# Clock_Multiplexer.net
KiCad netlist of a schematic drawn in EAGLE
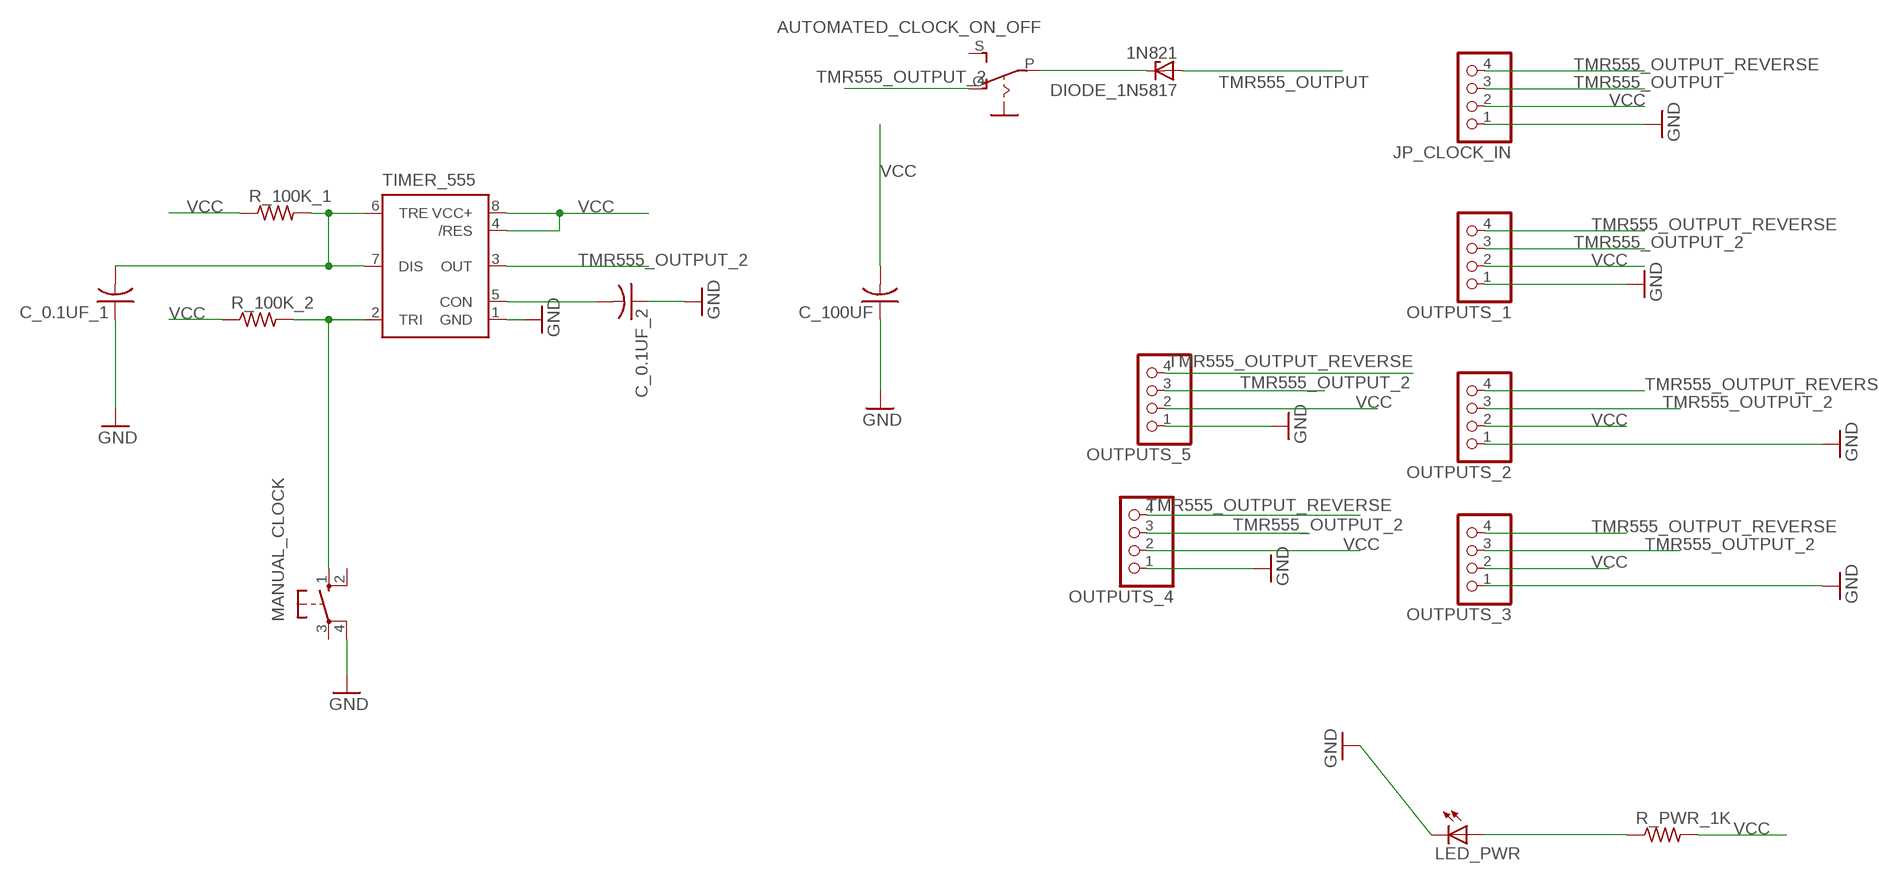
[diagram p0: schematic, sheet 1]

(export (version "E")
  (design (tool "Eeschema 10.0.6"))
  (components
    (comp (ref "AUTOMATED_CLOCK_ON_OFF")
      (value "EG1218S")
      (footprint "eagle-import:EG1218")
      (libsource (lib "eagle-import") (part "EG1218S"))
    )
    (comp (ref "C_0.1UF_1")
      (value "C-USC1206")
      (footprint "eagle-import:C1206")
      (libsource (lib "eagle-import") (part "C-USC1206"))
    )
    (comp (ref "C_0.1UF_2")
      (value "C-USC1206")
      (footprint "eagle-import:C1206")
      (libsource (lib "eagle-import") (part "C-USC1206"))
    )
    (comp (ref "C_100UF")
      (value "C-US025-030X050")
      (footprint "eagle-import:C025-030X050")
      (libsource (lib "eagle-import") (part "C-US025-030X050"))
    )
    (comp (ref "DIODE_1N5817")
      (value "1N821")
      (footprint "eagle-import:DO35Z10")
      (libsource (lib "eagle-import") (part "1N821"))
    )
    (comp (ref "JP_CLOCK_IN")
      (value "PINHD-1X4")
      (footprint "eagle-import:1X04")
      (libsource (lib "eagle-import") (part "PINHD-1X4"))
    )
    (comp (ref "LED_PWR")
      (value "LEDSMT1206")
      (footprint "eagle-import:1206")
      (libsource (lib "eagle-import") (part "LEDSMT1206"))
    )
    (comp (ref "MANUAL_CLOCK")
      (value "10-XX")
      (footprint "eagle-import:B3F-10XX")
      (fields (field (name "MPN") "B3F-1000"))
      (libsource (lib "eagle-import") (part "10-XX"))
    )
    (comp (ref "OUTPUTS_1")
      (value "PINHD-1X4")
      (footprint "eagle-import:1X04")
      (libsource (lib "eagle-import") (part "PINHD-1X4"))
    )
    (comp (ref "OUTPUTS_2")
      (value "PINHD-1X4")
      (footprint "eagle-import:1X04")
      (libsource (lib "eagle-import") (part "PINHD-1X4"))
    )
    (comp (ref "OUTPUTS_3")
      (value "PINHD-1X4")
      (footprint "eagle-import:1X04")
      (libsource (lib "eagle-import") (part "PINHD-1X4"))
    )
    (comp (ref "OUTPUTS_4")
      (value "PINHD-1X4")
      (footprint "eagle-import:1X04")
      (libsource (lib "eagle-import") (part "PINHD-1X4"))
    )
    (comp (ref "OUTPUTS_5")
      (value "PINHD-1X4")
      (footprint "eagle-import:1X04")
      (libsource (lib "eagle-import") (part "PINHD-1X4"))
    )
    (comp (ref "R_100K_1")
      (value "R-US_R1206")
      (footprint "eagle-import:R1206")
      (libsource (lib "eagle-import") (part "R-US_R1206"))
    )
    (comp (ref "R_100K_2")
      (value "R-US_R1206")
      (footprint "eagle-import:R1206")
      (libsource (lib "eagle-import") (part "R-US_R1206"))
    )
    (comp (ref "R_PWR_1K")
      (value "R-US_R1206")
      (footprint "eagle-import:R1206")
      (libsource (lib "eagle-import") (part "R-US_R1206"))
    )
    (comp (ref "TIMER_555")
      (value "NE555D")
      (footprint "eagle-import:SO08")
      (libsource (lib "eagle-import") (part "NE555D"))
    )
  )
  (nets
    (net (code "1") (name "/TMR555_OUTPUT") (class "Default")
      (node (ref "DIODE_1N5817") (pin "A") (pinfunction "A_A") (pintype "passive"))
      (node (ref "JP_CLOCK_IN") (pin "3") (pinfunction "3_3") (pintype "passive"))
    )
    (net (code "2") (name "/TMR555_OUTPUT_2") (class "Default")
      (node (ref "AUTOMATED_CLOCK_ON_OFF") (pin "O") (pinfunction "O_O") (pintype "passive"))
      (node (ref "OUTPUTS_1") (pin "3") (pinfunction "3_3") (pintype "passive"))
      (node (ref "OUTPUTS_2") (pin "3") (pinfunction "3_3") (pintype "passive"))
      (node (ref "OUTPUTS_3") (pin "3") (pinfunction "3_3") (pintype "passive"))
      (node (ref "OUTPUTS_4") (pin "3") (pinfunction "3_3") (pintype "passive"))
      (node (ref "OUTPUTS_5") (pin "3") (pinfunction "3_3") (pintype "passive"))
      (node (ref "TIMER_555") (pin "3") (pinfunction "OUT_3") (pintype "output"))
    )
    (net (code "3") (name "/TMR555_OUTPUT_REVERSE") (class "Default")
      (node (ref "JP_CLOCK_IN") (pin "4") (pinfunction "4_4") (pintype "passive"))
      (node (ref "OUTPUTS_1") (pin "4") (pinfunction "4_4") (pintype "passive"))
      (node (ref "OUTPUTS_2") (pin "4") (pinfunction "4_4") (pintype "passive"))
      (node (ref "OUTPUTS_3") (pin "4") (pinfunction "4_4") (pintype "passive"))
      (node (ref "OUTPUTS_4") (pin "4") (pinfunction "4_4") (pintype "passive"))
      (node (ref "OUTPUTS_5") (pin "4") (pinfunction "4_4") (pintype "passive"))
    )
    (net (code "4") (name "/VCC") (class "Default")
      (node (ref "C_100UF") (pin "2") (pinfunction "2_2") (pintype "passive"))
      (node (ref "JP_CLOCK_IN") (pin "2") (pinfunction "2_2") (pintype "passive"))
      (node (ref "OUTPUTS_1") (pin "2") (pinfunction "2_2") (pintype "passive"))
      (node (ref "OUTPUTS_2") (pin "2") (pinfunction "2_2") (pintype "passive"))
      (node (ref "OUTPUTS_3") (pin "2") (pinfunction "2_2") (pintype "passive"))
      (node (ref "OUTPUTS_4") (pin "2") (pinfunction "2_2") (pintype "passive"))
      (node (ref "OUTPUTS_5") (pin "2") (pinfunction "2_2") (pintype "passive"))
      (node (ref "R_100K_1") (pin "1") (pinfunction "1_1") (pintype "passive"))
      (node (ref "R_100K_2") (pin "1") (pinfunction "1_1") (pintype "passive"))
      (node (ref "R_PWR_1K") (pin "2") (pinfunction "2_2") (pintype "passive"))
      (node (ref "TIMER_555") (pin "4") (pinfunction "/RES_4") (pintype "input"))
      (node (ref "TIMER_555") (pin "8") (pinfunction "VCC+_8") (pintype "power_in"))
    )
    (net (code "5") (name "GND") (class "Default")
      (node (ref "C_0.1UF_1") (pin "1") (pinfunction "1_1") (pintype "passive"))
      (node (ref "C_0.1UF_2") (pin "1") (pinfunction "1_1") (pintype "passive"))
      (node (ref "C_100UF") (pin "1") (pinfunction "1_1") (pintype "passive"))
      (node (ref "JP_CLOCK_IN") (pin "1") (pinfunction "1_1") (pintype "passive"))
      (node (ref "LED_PWR") (pin "C") (pinfunction "C_C") (pintype "passive"))
      (node (ref "MANUAL_CLOCK") (pin "4") (pinfunction "P1_4") (pintype "passive"))
      (node (ref "OUTPUTS_1") (pin "1") (pinfunction "1_1") (pintype "passive"))
      (node (ref "OUTPUTS_2") (pin "1") (pinfunction "1_1") (pintype "passive"))
      (node (ref "OUTPUTS_3") (pin "1") (pinfunction "1_1") (pintype "passive"))
      (node (ref "OUTPUTS_4") (pin "1") (pinfunction "1_1") (pintype "passive"))
      (node (ref "OUTPUTS_5") (pin "1") (pinfunction "1_1") (pintype "passive"))
      (node (ref "TIMER_555") (pin "1") (pinfunction "GND_1") (pintype "power_in"))
    )
    (net (code "6") (name "Net-(AUTOMATED_CLOCK_ON_OFF-PadP)") (class "Default")
      (node (ref "AUTOMATED_CLOCK_ON_OFF") (pin "P") (pinfunction "P_P") (pintype "passive"))
      (node (ref "DIODE_1N5817") (pin "C") (pinfunction "C_C") (pintype "passive"))
    )
    (net (code "7") (name "Net-(LED_PWR-PadA)") (class "Default")
      (node (ref "LED_PWR") (pin "A") (pinfunction "A_A") (pintype "passive"))
      (node (ref "R_PWR_1K") (pin "1") (pinfunction "1_1") (pintype "passive"))
    )
    (net (code "8") (name "Net-(MANUAL_CLOCK-S)") (class "Default")
      (node (ref "MANUAL_CLOCK") (pin "1") (pinfunction "S_1") (pintype "passive"))
      (node (ref "R_100K_2") (pin "2") (pinfunction "2_2") (pintype "passive"))
      (node (ref "TIMER_555") (pin "2") (pinfunction "TRI_2") (pintype "input"))
    )
    (net (code "9") (name "Net-(TIMER_555-CON)") (class "Default")
      (node (ref "C_0.1UF_2") (pin "2") (pinfunction "2_2") (pintype "passive"))
      (node (ref "TIMER_555") (pin "5") (pinfunction "CON_5") (pintype "input"))
    )
    (net (code "10") (name "Net-(TIMER_555-DIS)") (class "Default")
      (node (ref "C_0.1UF_1") (pin "2") (pinfunction "2_2") (pintype "passive"))
      (node (ref "R_100K_1") (pin "2") (pinfunction "2_2") (pintype "passive"))
      (node (ref "TIMER_555") (pin "6") (pinfunction "TRE_6") (pintype "input"))
      (node (ref "TIMER_555") (pin "7") (pinfunction "DIS_7") (pintype "input"))
    )
    (net (code "11") (name "unconnected-(AUTOMATED_CLOCK_ON_OFF-PadS)") (class "Default")
      (node (ref "AUTOMATED_CLOCK_ON_OFF") (pin "S") (pinfunction "S_S") (pintype "passive"))
    )
    (net (code "12") (name "unconnected-(MANUAL_CLOCK-P-Pad3)") (class "Default")
      (node (ref "MANUAL_CLOCK") (pin "3") (pinfunction "P_3") (pintype "passive"))
    )
    (net (code "13") (name "unconnected-(MANUAL_CLOCK-S1-Pad2)") (class "Default")
      (node (ref "MANUAL_CLOCK") (pin "2") (pinfunction "S1_2") (pintype "passive"))
    )
  )
)
